# PMS_alpha_v0_1.net
KiCad netlist of a schematic drawn in EAGLE
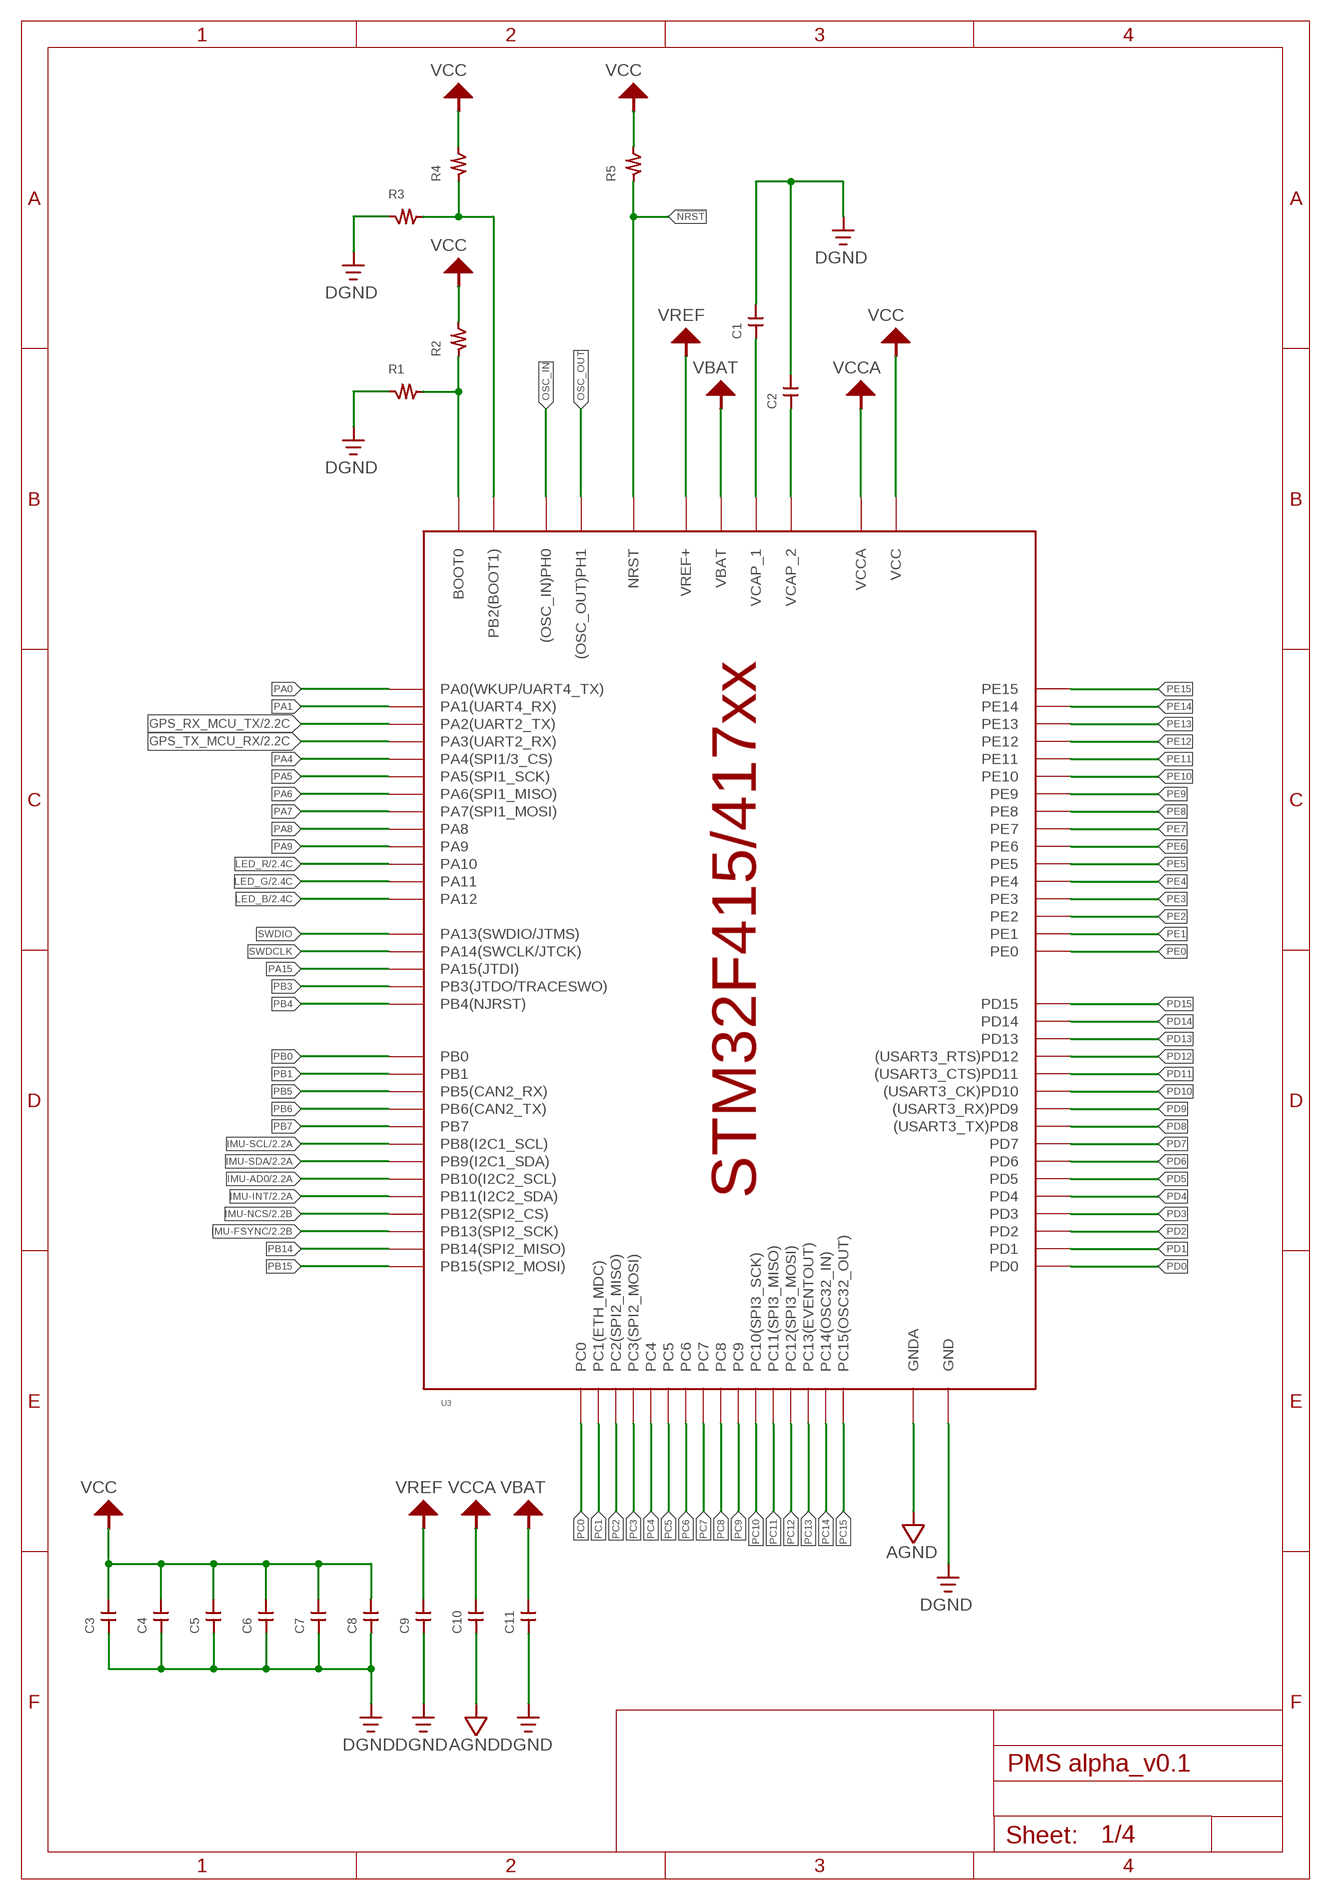
[diagram p0: schematic, sheet 1]
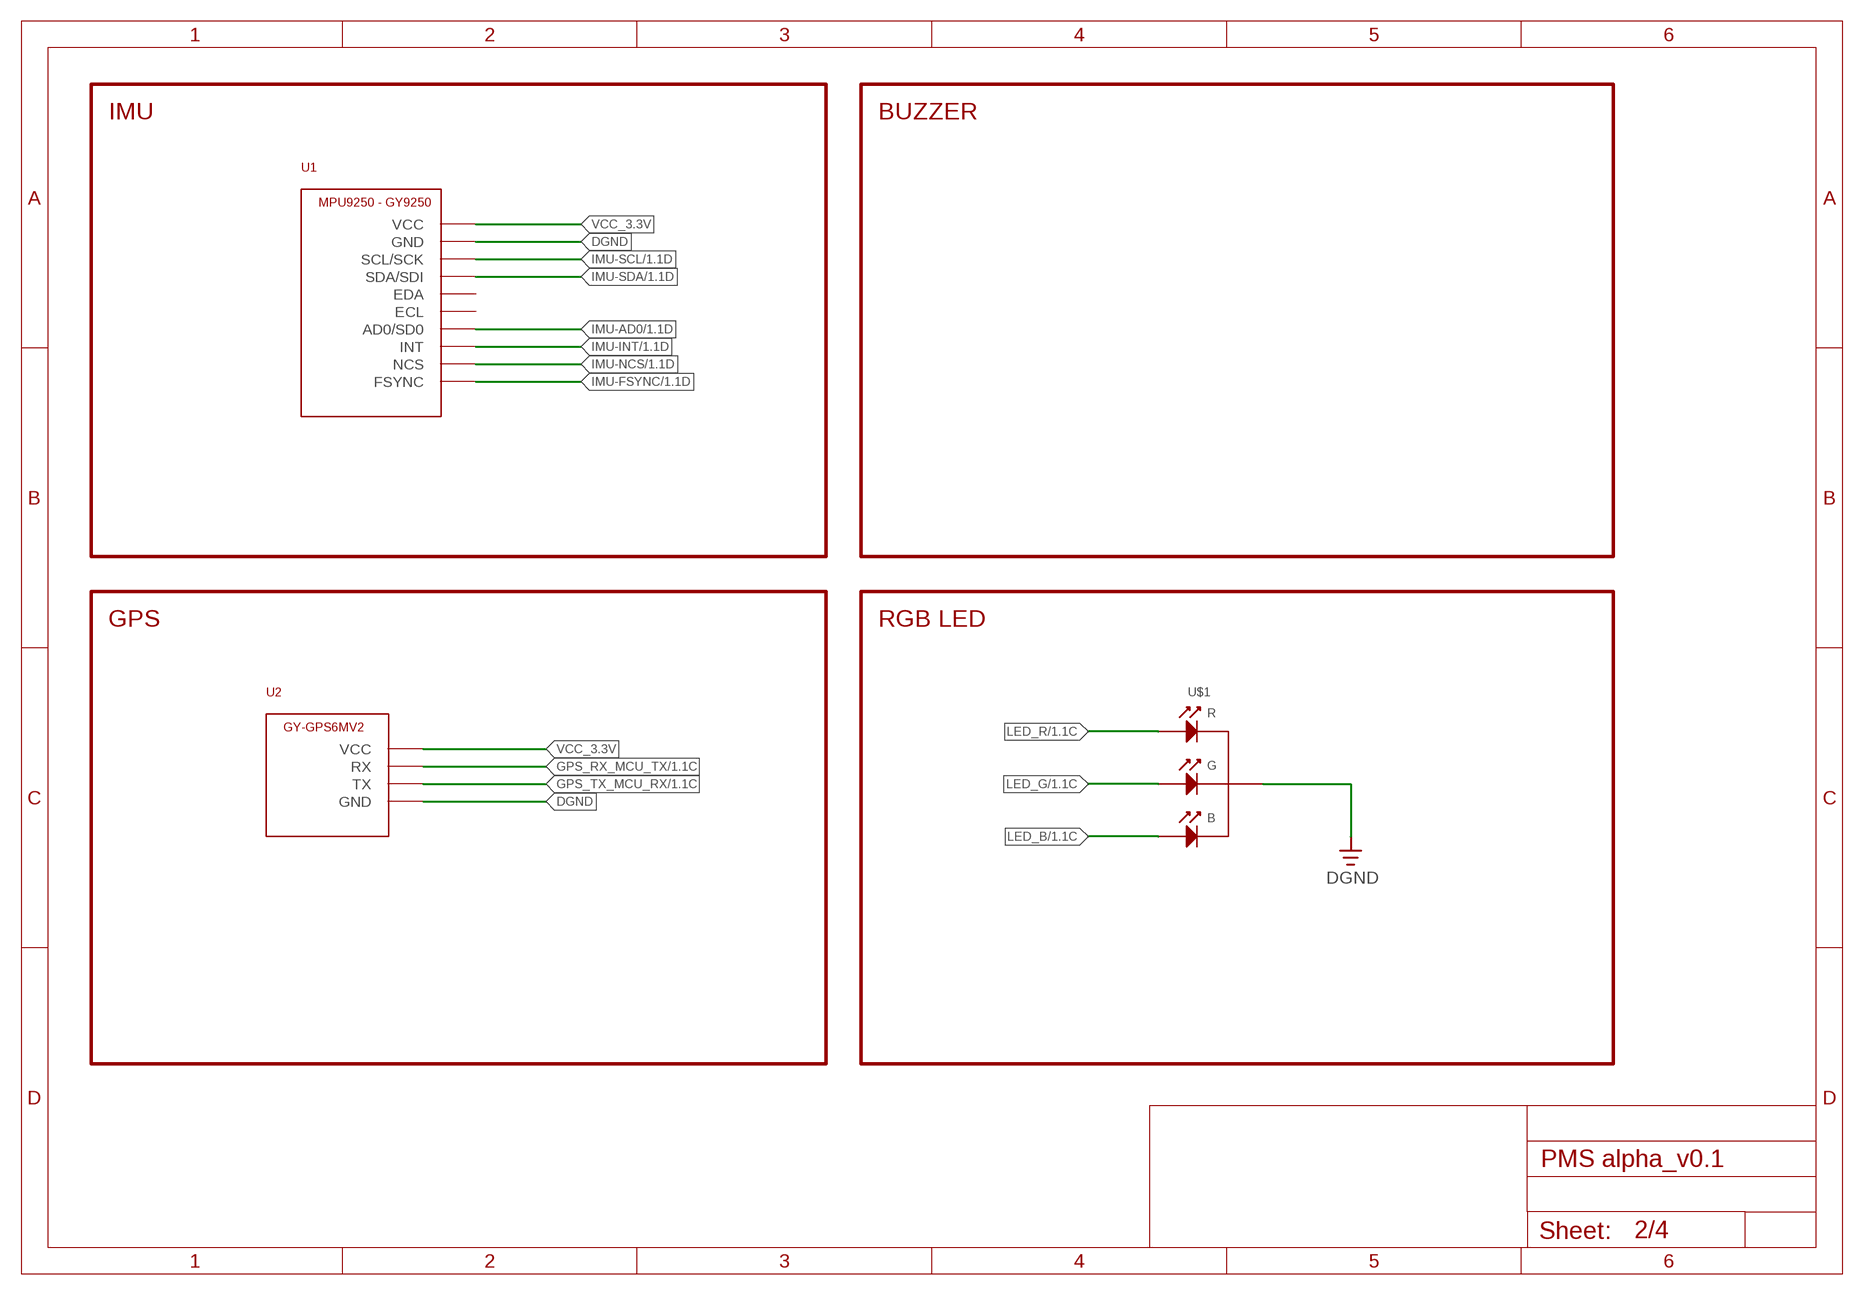
[diagram p1: schematic, sheet 2]
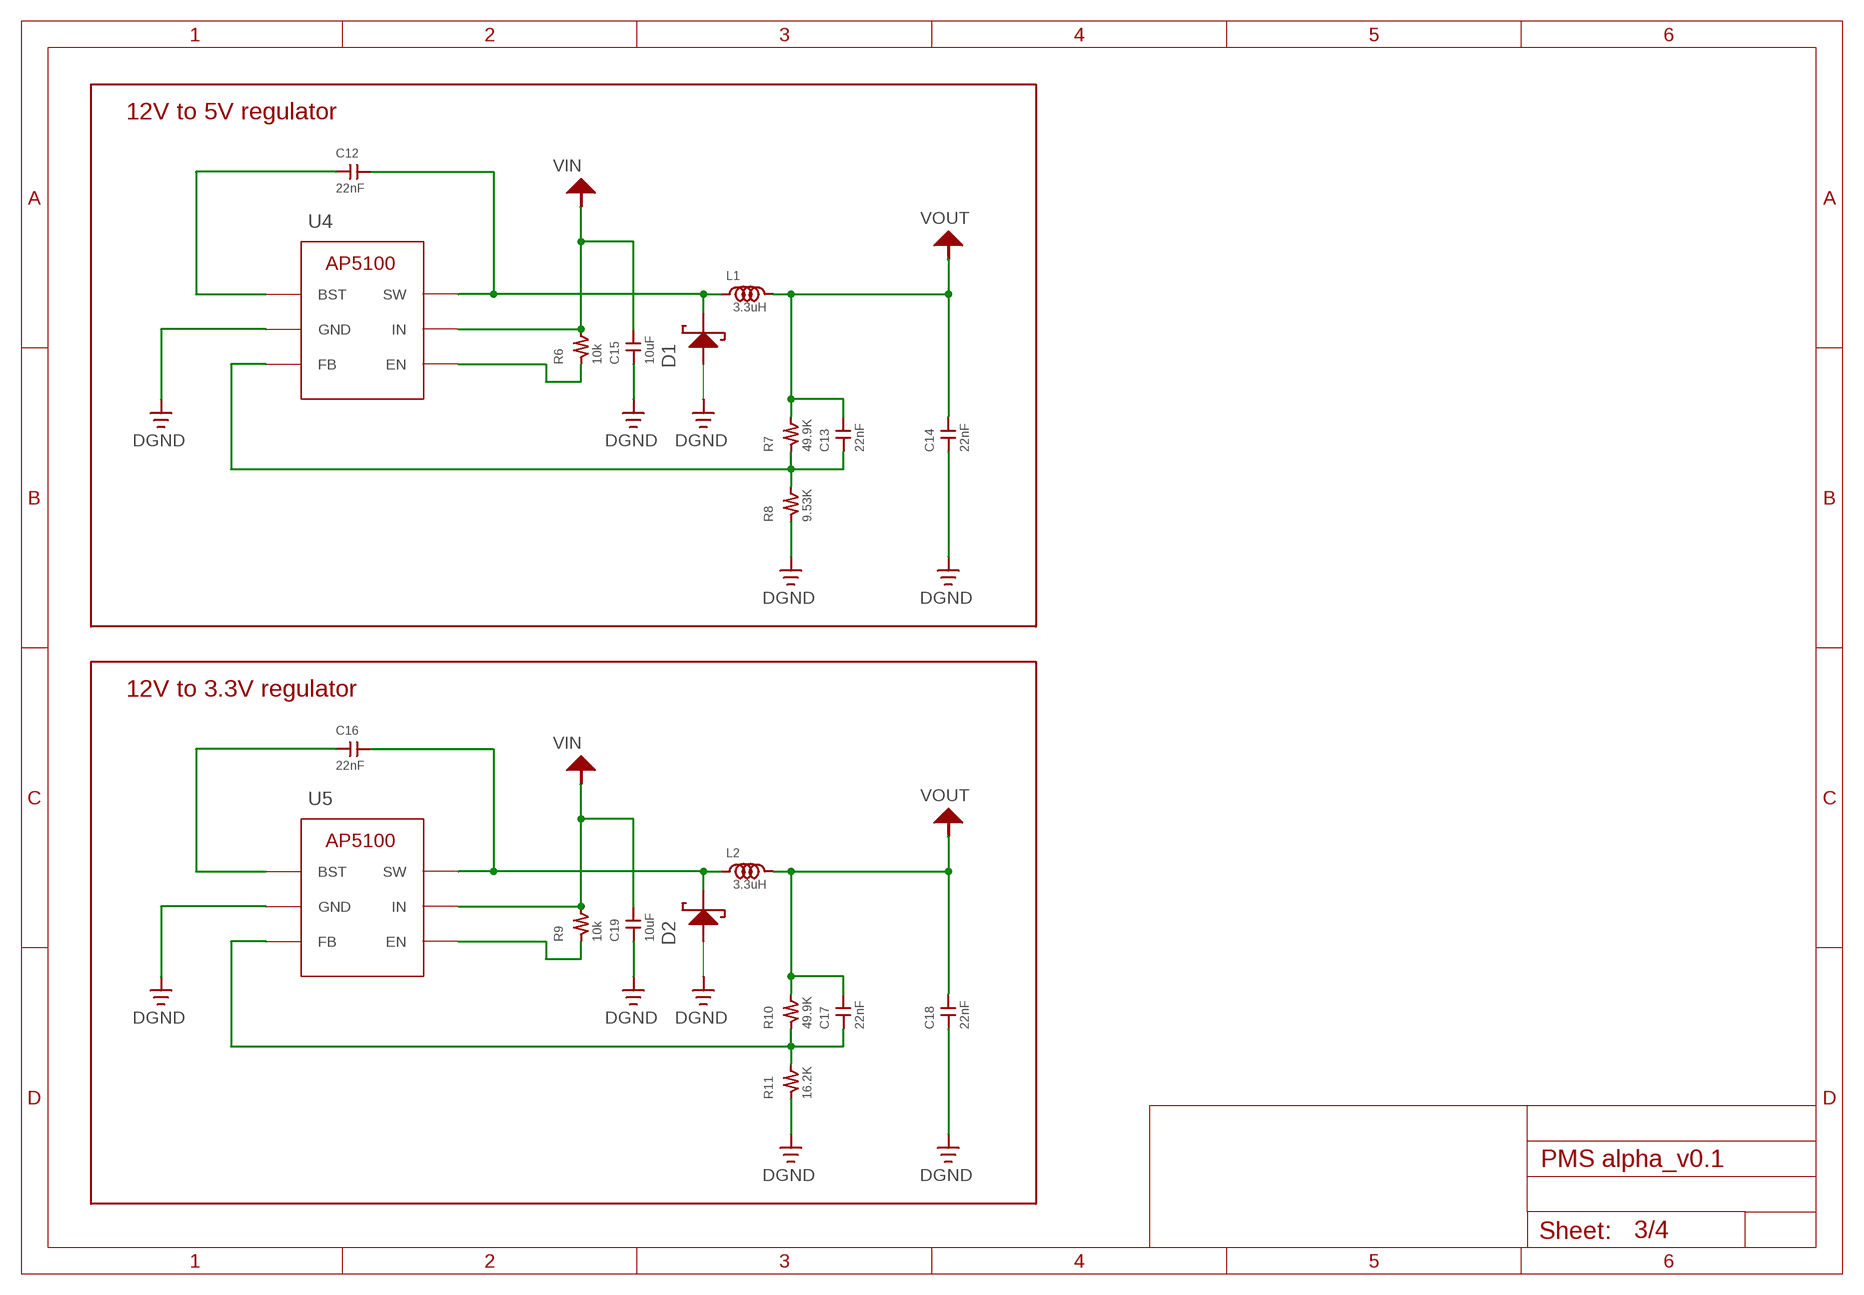
[diagram p2: schematic, sheet 3]
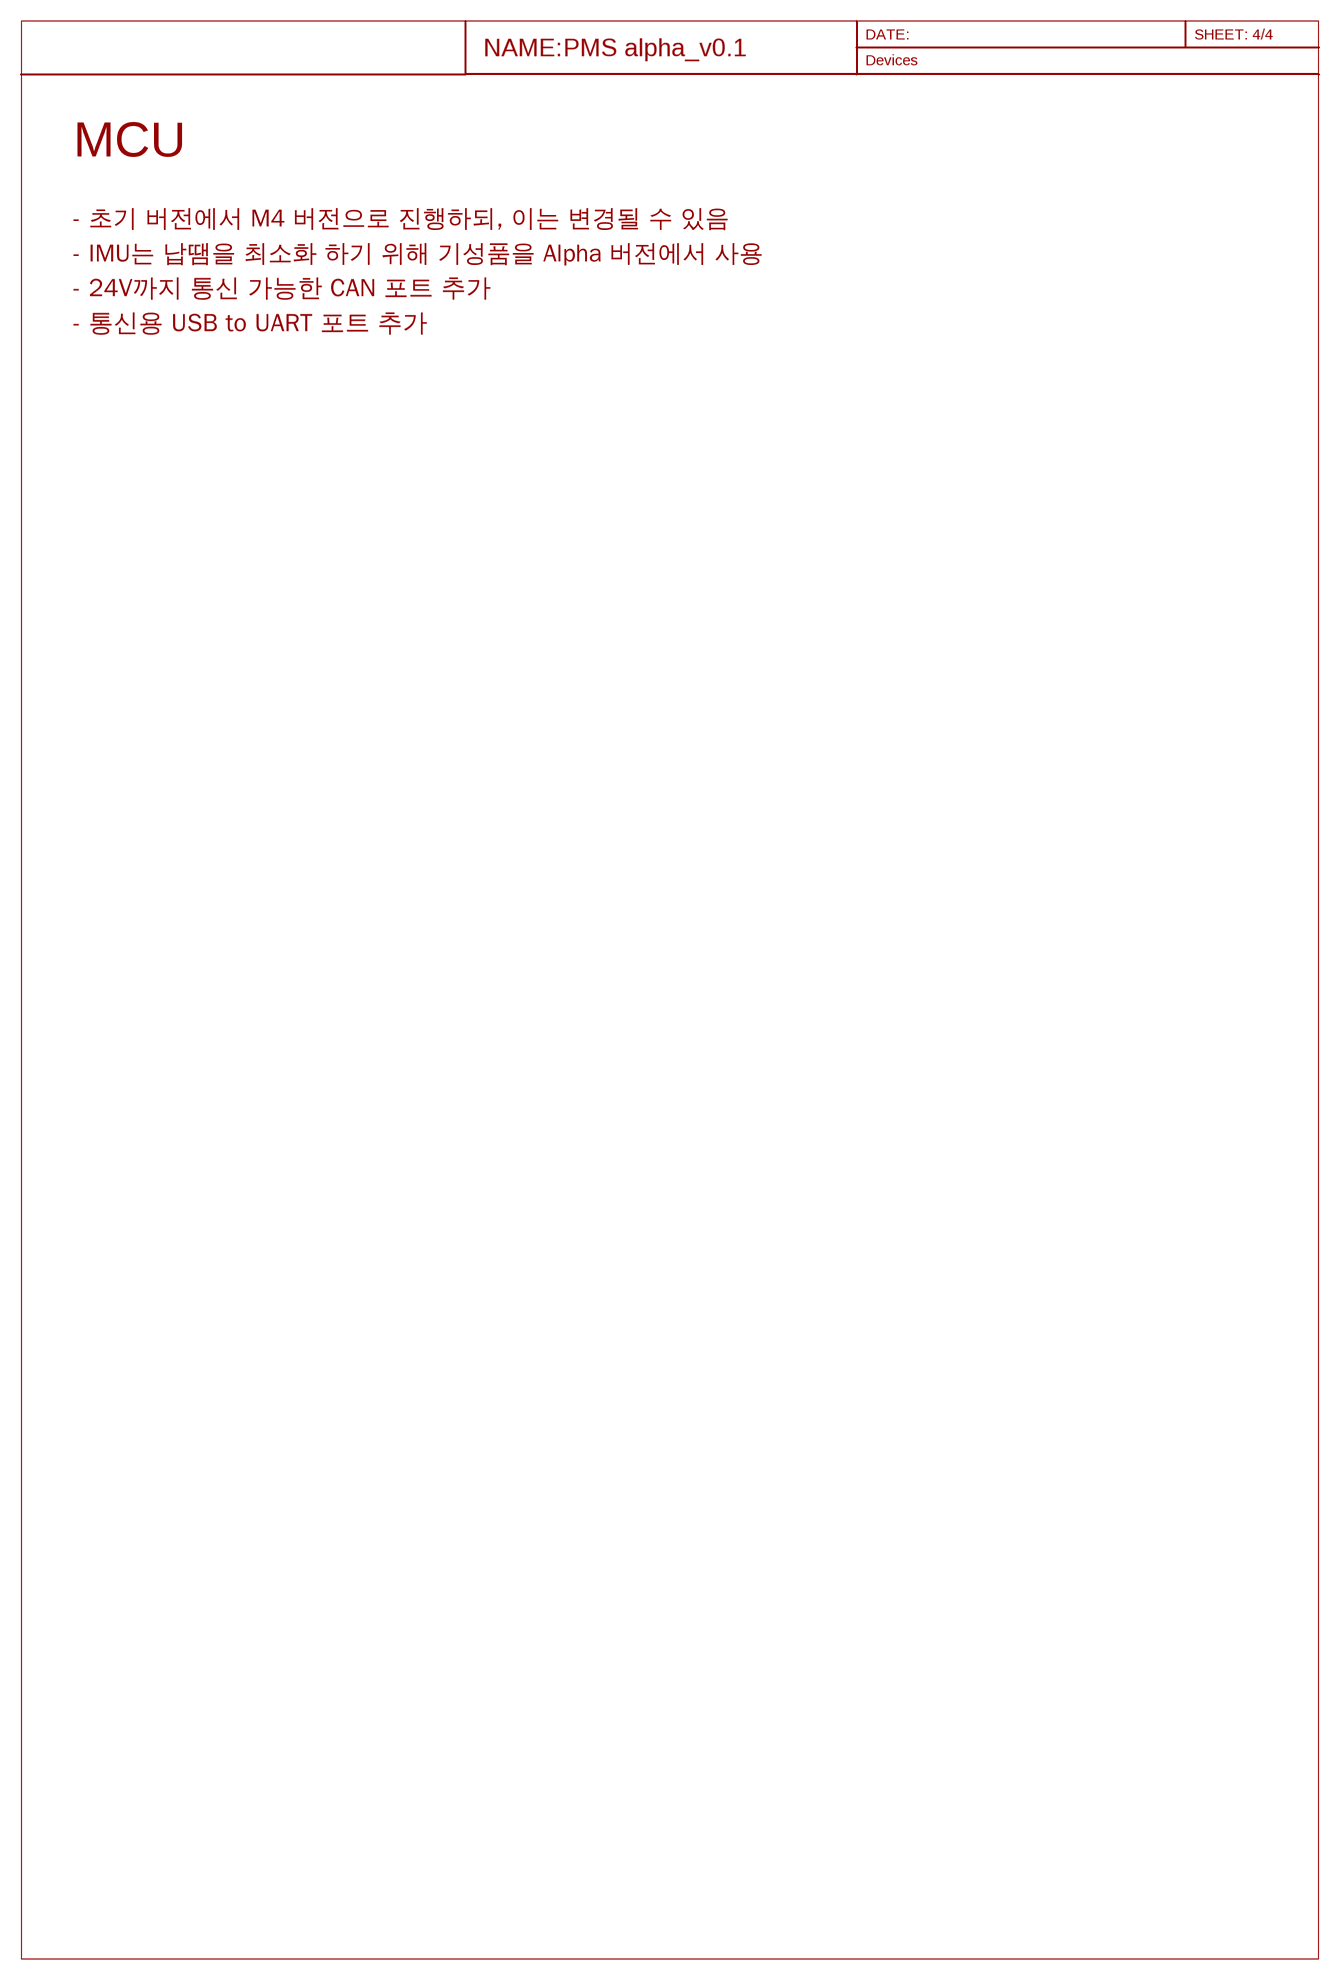
[diagram p3: schematic, sheet 4]

(export (version "E")
  (design (tool "Eeschema 10.0.6"))
  (components
    (comp (ref "U$1")
      (value "RGB_COM_K")
      (footprint "eagle-import:RGB_4PIN_2.5MM")
      (libsource (lib "eagle-import") (part "RGB_COM_K"))
    )
    (comp (ref "U1")
      (value "MPU-9250")
      (footprint "eagle-import:GY-9250")
      (libsource (lib "eagle-import") (part "MPU-9250"))
    )
    (comp (ref "U2")
      (value "GPS6MV2")
      (footprint "eagle-import:PAD_2.5MM")
      (libsource (lib "eagle-import") (part "GPS6MV2"))
    )
    (comp (ref "C1")
      (value "CAPACITOR_CHIP2012")
      (footprint "eagle-import:2012")
      (libsource (lib "eagle-import") (part "CAPACITOR_CHIP2012"))
    )
    (comp (ref "C2")
      (value "CAPACITOR_CHIP2012")
      (footprint "eagle-import:2012")
      (libsource (lib "eagle-import") (part "CAPACITOR_CHIP2012"))
    )
    (comp (ref "C3")
      (value "CAPACITOR_CHIP2012")
      (footprint "eagle-import:2012")
      (libsource (lib "eagle-import") (part "CAPACITOR_CHIP2012"))
    )
    (comp (ref "C4")
      (value "CAPACITOR_CHIP2012")
      (footprint "eagle-import:2012")
      (libsource (lib "eagle-import") (part "CAPACITOR_CHIP2012"))
    )
    (comp (ref "C5")
      (value "CAPACITOR_CHIP2012")
      (footprint "eagle-import:2012")
      (libsource (lib "eagle-import") (part "CAPACITOR_CHIP2012"))
    )
    (comp (ref "C6")
      (value "CAPACITOR_CHIP2012")
      (footprint "eagle-import:2012")
      (libsource (lib "eagle-import") (part "CAPACITOR_CHIP2012"))
    )
    (comp (ref "C7")
      (value "CAPACITOR_CHIP2012")
      (footprint "eagle-import:2012")
      (libsource (lib "eagle-import") (part "CAPACITOR_CHIP2012"))
    )
    (comp (ref "C8")
      (value "CAPACITOR_CHIP2012")
      (footprint "eagle-import:2012")
      (libsource (lib "eagle-import") (part "CAPACITOR_CHIP2012"))
    )
    (comp (ref "C9")
      (value "CAPACITOR_CHIP2012")
      (footprint "eagle-import:2012")
      (libsource (lib "eagle-import") (part "CAPACITOR_CHIP2012"))
    )
    (comp (ref "C10")
      (value "CAPACITOR_CHIP2012")
      (footprint "eagle-import:2012")
      (libsource (lib "eagle-import") (part "CAPACITOR_CHIP2012"))
    )
    (comp (ref "C11")
      (value "CAPACITOR_CHIP2012")
      (footprint "eagle-import:2012")
      (libsource (lib "eagle-import") (part "CAPACITOR_CHIP2012"))
    )
    (comp (ref "R1")
      (value "RESISTOR_CHIP_2012")
      (footprint "eagle-import:2012")
      (libsource (lib "eagle-import") (part "RESISTOR_CHIP_2012"))
    )
    (comp (ref "R2")
      (value "RESISTOR_CHIP_2012")
      (footprint "eagle-import:2012")
      (libsource (lib "eagle-import") (part "RESISTOR_CHIP_2012"))
    )
    (comp (ref "R3")
      (value "RESISTOR_CHIP_2012")
      (footprint "eagle-import:2012")
      (libsource (lib "eagle-import") (part "RESISTOR_CHIP_2012"))
    )
    (comp (ref "R4")
      (value "RESISTOR_CHIP_2012")
      (footprint "eagle-import:2012")
      (libsource (lib "eagle-import") (part "RESISTOR_CHIP_2012"))
    )
    (comp (ref "R5")
      (value "RESISTOR_CHIP_2012")
      (footprint "eagle-import:2012")
      (libsource (lib "eagle-import") (part "RESISTOR_CHIP_2012"))
    )
    (comp (ref "U3")
      (value "STM32F415/417")
      (footprint "eagle-import:LQFP100")
      (libsource (lib "eagle-import") (part "STM32F415/417"))
    )
    (comp (ref "C12")
      (value "22nF")
      (footprint "eagle-import:2012")
      (libsource (lib "eagle-import") (part "CAPACITOR_CHIP2012"))
    )
    (comp (ref "C13")
      (value "22nF")
      (footprint "eagle-import:2012")
      (libsource (lib "eagle-import") (part "CAPACITOR_CHIP2012"))
    )
    (comp (ref "C14")
      (value "22nF")
      (footprint "eagle-import:2012")
      (libsource (lib "eagle-import") (part "CAPACITOR_CHIP2012"))
    )
    (comp (ref "C15")
      (value "10uF")
      (footprint "eagle-import:2012")
      (libsource (lib "eagle-import") (part "CAPACITOR_CHIP2012"))
    )
    (comp (ref "C16")
      (value "22nF")
      (footprint "eagle-import:2012")
      (libsource (lib "eagle-import") (part "CAPACITOR_CHIP2012"))
    )
    (comp (ref "C17")
      (value "22nF")
      (footprint "eagle-import:2012")
      (libsource (lib "eagle-import") (part "CAPACITOR_CHIP2012"))
    )
    (comp (ref "C18")
      (value "22nF")
      (footprint "eagle-import:2012")
      (libsource (lib "eagle-import") (part "CAPACITOR_CHIP2012"))
    )
    (comp (ref "C19")
      (value "10uF")
      (footprint "eagle-import:2012")
      (libsource (lib "eagle-import") (part "CAPACITOR_CHIP2012"))
    )
    (comp (ref "D1")
      (value "BAT60JFILM")
      (footprint "eagle-import:SOD323")
      (libsource (lib "eagle-import") (part "BAT60JFILM"))
    )
    (comp (ref "D2")
      (value "BAT60JFILM")
      (footprint "eagle-import:SOD323")
      (libsource (lib "eagle-import") (part "BAT60JFILM"))
    )
    (comp (ref "L1")
      (value "3.3uH")
      (footprint "eagle-import:2012")
      (libsource (lib "eagle-import") (part "INDUCTOR2012"))
    )
    (comp (ref "L2")
      (value "3.3uH")
      (footprint "eagle-import:2012")
      (libsource (lib "eagle-import") (part "INDUCTOR2012"))
    )
    (comp (ref "R6")
      (value "10k")
      (footprint "eagle-import:2012")
      (libsource (lib "eagle-import") (part "RESISTOR_CHIP_2012"))
    )
    (comp (ref "R7")
      (value "49.9K")
      (footprint "eagle-import:2012")
      (libsource (lib "eagle-import") (part "RESISTOR_CHIP_2012"))
    )
    (comp (ref "R8")
      (value "9.53K")
      (footprint "eagle-import:2012")
      (libsource (lib "eagle-import") (part "RESISTOR_CHIP_2012"))
    )
    (comp (ref "R9")
      (value "10k")
      (footprint "eagle-import:2012")
      (libsource (lib "eagle-import") (part "RESISTOR_CHIP_2012"))
    )
    (comp (ref "R10")
      (value "49.9K")
      (footprint "eagle-import:2012")
      (libsource (lib "eagle-import") (part "RESISTOR_CHIP_2012"))
    )
    (comp (ref "R11")
      (value "16.2K")
      (footprint "eagle-import:2012")
      (libsource (lib "eagle-import") (part "RESISTOR_CHIP_2012"))
    )
    (comp (ref "U4")
      (value "AP5100")
      (footprint "eagle-import:SOT-26")
      (libsource (lib "eagle-import") (part "AP5100"))
    )
    (comp (ref "U5")
      (value "AP5100")
      (footprint "eagle-import:SOT-26")
      (libsource (lib "eagle-import") (part "AP5100"))
    )
  )
  (nets
    (net (code "1") (name "AGND") (class "Default")
      (node (ref "C10") (pin "P$1") (pinfunction "P$1_P$1") (pintype "passive"))
      (node (ref "U3") (pin "P$20") (pinfunction "GNDA_P$20") (pintype "power_in"))
    )
    (net (code "2") (name "DGND") (class "Default")
      (node (ref "C1") (pin "P$2") (pinfunction "P$2_P$2") (pintype "passive"))
      (node (ref "C11") (pin "P$1") (pinfunction "P$1_P$1") (pintype "passive"))
      (node (ref "C14") (pin "P$1") (pinfunction "P$1_P$1") (pintype "passive"))
      (node (ref "C15") (pin "P$1") (pinfunction "P$1_P$1") (pintype "passive"))
      (node (ref "C18") (pin "P$1") (pinfunction "P$1_P$1") (pintype "passive"))
      (node (ref "C19") (pin "P$1") (pinfunction "P$1_P$1") (pintype "passive"))
      (node (ref "C2") (pin "P$2") (pinfunction "P$2_P$2") (pintype "passive"))
      (node (ref "C3") (pin "P$1") (pinfunction "P$1_P$1") (pintype "passive"))
      (node (ref "C4") (pin "P$1") (pinfunction "P$1_P$1") (pintype "passive"))
      (node (ref "C5") (pin "P$1") (pinfunction "P$1_P$1") (pintype "passive"))
      (node (ref "C6") (pin "P$1") (pinfunction "P$1_P$1") (pintype "passive"))
      (node (ref "C7") (pin "P$1") (pinfunction "P$1_P$1") (pintype "passive"))
      (node (ref "C8") (pin "P$1") (pinfunction "P$1_P$1") (pintype "passive"))
      (node (ref "C9") (pin "P$1") (pinfunction "P$1_P$1") (pintype "passive"))
      (node (ref "D1") (pin "A") (pinfunction "A_A") (pintype "passive"))
      (node (ref "D2") (pin "A") (pinfunction "A_A") (pintype "passive"))
      (node (ref "R1") (pin "P$1") (pinfunction "P$1_P$1") (pintype "passive"))
      (node (ref "R11") (pin "P$1") (pinfunction "P$1_P$1") (pintype "passive"))
      (node (ref "R3") (pin "P$1") (pinfunction "P$1_P$1") (pintype "passive"))
      (node (ref "R8") (pin "P$1") (pinfunction "P$1_P$1") (pintype "passive"))
      (node (ref "U$1") (pin "P$4") (pinfunction "K_P$4") (pintype "bidirectional"))
      (node (ref "U1") (pin "P$2") (pinfunction "GND_P$2") (pintype "power_in"))
      (node (ref "U2") (pin "P$4") (pinfunction "GND_P$4") (pintype "power_in"))
      (node (ref "U3") (pin "P$10") (pinfunction "GND_P$10") (pintype "power_in"))
      (node (ref "U3") (pin "P$27") (pinfunction "GND_P$27") (pintype "power_in"))
      (node (ref "U3") (pin "P$74") (pinfunction "GND_P$74") (pintype "power_in"))
      (node (ref "U3") (pin "P$99") (pinfunction "GND_P$99") (pintype "power_in"))
      (node (ref "U4") (pin "P2") (pinfunction "GND_P2") (pintype "power_in"))
      (node (ref "U5") (pin "P2") (pinfunction "GND_P2") (pintype "power_in"))
    )
    (net (code "3") (name "GPS_RX_MCU_TX") (class "Default")
      (node (ref "U2") (pin "P$2") (pinfunction "RX_P$2") (pintype "bidirectional"))
      (node (ref "U3") (pin "P$25") (pinfunction "PA2(UART2_TX)_P$25") (pintype "bidirectional"))
    )
    (net (code "4") (name "GPS_TX_MCU_RX") (class "Default")
      (node (ref "U2") (pin "P$3") (pinfunction "TX_P$3") (pintype "bidirectional"))
      (node (ref "U3") (pin "P$26") (pinfunction "PA3(UART2_RX)_P$26") (pintype "bidirectional"))
    )
    (net (code "5") (name "IMU-AD0") (class "Default")
      (node (ref "U1") (pin "P$7") (pinfunction "AD0/SD0_P$7") (pintype "bidirectional"))
      (node (ref "U3") (pin "P$47") (pinfunction "PB10(I2C2_SCL)_P$47") (pintype "bidirectional"))
    )
    (net (code "6") (name "IMU-FSYNC") (class "Default")
      (node (ref "U1") (pin "P$10") (pinfunction "FSYNC_P$10") (pintype "bidirectional"))
      (node (ref "U3") (pin "P$52") (pinfunction "PB13(SPI2_SCK)_P$52") (pintype "bidirectional"))
    )
    (net (code "7") (name "IMU-INT") (class "Default")
      (node (ref "U1") (pin "P$8") (pinfunction "INT_P$8") (pintype "bidirectional"))
      (node (ref "U3") (pin "P$48") (pinfunction "PB11(I2C2_SDA)_P$48") (pintype "bidirectional"))
    )
    (net (code "8") (name "IMU-NCS") (class "Default")
      (node (ref "U1") (pin "P$9") (pinfunction "NCS_P$9") (pintype "bidirectional"))
      (node (ref "U3") (pin "P$51") (pinfunction "PB12(SPI2_CS)_P$51") (pintype "bidirectional"))
    )
    (net (code "9") (name "IMU-SCL") (class "Default")
      (node (ref "U1") (pin "P$3") (pinfunction "SCL/SCK_P$3") (pintype "bidirectional"))
      (node (ref "U3") (pin "P$95") (pinfunction "PB8(I2C1_SCL)_P$95") (pintype "bidirectional"))
    )
    (net (code "10") (name "IMU-SDA") (class "Default")
      (node (ref "U1") (pin "P$4") (pinfunction "SDA/SDI_P$4") (pintype "bidirectional"))
      (node (ref "U3") (pin "P$96") (pinfunction "PB9(I2C1_SDA)_P$96") (pintype "bidirectional"))
    )
    (net (code "11") (name "LED_B") (class "Default")
      (node (ref "U$1") (pin "P$3") (pinfunction "A_P$3") (pintype "bidirectional"))
      (node (ref "U3") (pin "P$71") (pinfunction "PA12_P$71") (pintype "bidirectional"))
    )
    (net (code "12") (name "LED_G") (class "Default")
      (node (ref "U$1") (pin "P$2") (pinfunction "A_P$2") (pintype "bidirectional"))
      (node (ref "U3") (pin "P$70") (pinfunction "PA11_P$70") (pintype "bidirectional"))
    )
    (net (code "13") (name "LED_R") (class "Default")
      (node (ref "U$1") (pin "P$1") (pinfunction "A_P$1") (pintype "bidirectional"))
      (node (ref "U3") (pin "P$69") (pinfunction "PA10_P$69") (pintype "bidirectional"))
    )
    (net (code "14") (name "Net-(U3-BOOT0)") (class "Default")
      (node (ref "R1") (pin "P$2") (pinfunction "P$2_P$2") (pintype "passive"))
      (node (ref "R2") (pin "P$1") (pinfunction "P$1_P$1") (pintype "passive"))
      (node (ref "U3") (pin "P$94") (pinfunction "BOOT0_P$94") (pintype "bidirectional"))
    )
    (net (code "15") (name "Net-(U3-PB2(BOOT1))") (class "Default")
      (node (ref "R3") (pin "P$2") (pinfunction "P$2_P$2") (pintype "passive"))
      (node (ref "R4") (pin "P$1") (pinfunction "P$1_P$1") (pintype "passive"))
      (node (ref "U3") (pin "P$37") (pinfunction "PB2(BOOT1)_P$37") (pintype "bidirectional"))
    )
    (net (code "16") (name "Net-(U3-VCAP_1)") (class "Default")
      (node (ref "C1") (pin "P$1") (pinfunction "P$1_P$1") (pintype "passive"))
      (node (ref "U3") (pin "P$49") (pinfunction "VCAP_1_P$49") (pintype "power_in"))
    )
    (net (code "17") (name "Net-(U3-VCAP_2)") (class "Default")
      (node (ref "C2") (pin "P$1") (pinfunction "P$1_P$1") (pintype "passive"))
      (node (ref "U3") (pin "P$73") (pinfunction "VCAP_2_P$73") (pintype "power_in"))
    )
    (net (code "18") (name "Net-(U4-BST)") (class "Default")
      (node (ref "C12") (pin "P$1") (pinfunction "P$1_P$1") (pintype "passive"))
      (node (ref "U4") (pin "P1") (pinfunction "BST_P1") (pintype "bidirectional"))
    )
    (net (code "19") (name "Net-(U4-EN)") (class "Default")
      (node (ref "R6") (pin "P$1") (pinfunction "P$1_P$1") (pintype "passive"))
      (node (ref "U4") (pin "P4") (pinfunction "EN_P4") (pintype "bidirectional"))
    )
    (net (code "20") (name "Net-(U4-FB)") (class "Default")
      (node (ref "C13") (pin "P$1") (pinfunction "P$1_P$1") (pintype "passive"))
      (node (ref "R7") (pin "P$1") (pinfunction "P$1_P$1") (pintype "passive"))
      (node (ref "R8") (pin "P$2") (pinfunction "P$2_P$2") (pintype "passive"))
      (node (ref "U4") (pin "P3") (pinfunction "FB_P3") (pintype "bidirectional"))
    )
    (net (code "21") (name "Net-(U4-SW)") (class "Default")
      (node (ref "C12") (pin "P$2") (pinfunction "P$2_P$2") (pintype "passive"))
      (node (ref "D1") (pin "K") (pinfunction "K_K") (pintype "passive"))
      (node (ref "L1") (pin "P$1") (pinfunction "P$1_P$1") (pintype "passive"))
      (node (ref "U4") (pin "P6") (pinfunction "SW_P6") (pintype "bidirectional"))
    )
    (net (code "22") (name "Net-(U5-BST)") (class "Default")
      (node (ref "C16") (pin "P$1") (pinfunction "P$1_P$1") (pintype "passive"))
      (node (ref "U5") (pin "P1") (pinfunction "BST_P1") (pintype "bidirectional"))
    )
    (net (code "23") (name "Net-(U5-EN)") (class "Default")
      (node (ref "R9") (pin "P$1") (pinfunction "P$1_P$1") (pintype "passive"))
      (node (ref "U5") (pin "P4") (pinfunction "EN_P4") (pintype "bidirectional"))
    )
    (net (code "24") (name "Net-(U5-FB)") (class "Default")
      (node (ref "C17") (pin "P$1") (pinfunction "P$1_P$1") (pintype "passive"))
      (node (ref "R10") (pin "P$1") (pinfunction "P$1_P$1") (pintype "passive"))
      (node (ref "R11") (pin "P$2") (pinfunction "P$2_P$2") (pintype "passive"))
      (node (ref "U5") (pin "P3") (pinfunction "FB_P3") (pintype "bidirectional"))
    )
    (net (code "25") (name "Net-(U5-SW)") (class "Default")
      (node (ref "C16") (pin "P$2") (pinfunction "P$2_P$2") (pintype "passive"))
      (node (ref "D2") (pin "K") (pinfunction "K_K") (pintype "passive"))
      (node (ref "L2") (pin "P$1") (pinfunction "P$1_P$1") (pintype "passive"))
      (node (ref "U5") (pin "P6") (pinfunction "SW_P6") (pintype "bidirectional"))
    )
    (net (code "26") (name "OSC_IN") (class "Default")
      (node (ref "U3") (pin "P$12") (pinfunction "(OSC_IN)PH0_P$12") (pintype "bidirectional"))
    )
    (net (code "27") (name "OSC_OUT") (class "Default")
      (node (ref "U3") (pin "P$13") (pinfunction "(OSC_OUT)PH1_P$13") (pintype "bidirectional"))
    )
    (net (code "28") (name "PA0") (class "Default")
      (node (ref "U3") (pin "P$23") (pinfunction "PA0(WKUP/UART4_TX)_P$23") (pintype "bidirectional"))
    )
    (net (code "29") (name "PA1") (class "Default")
      (node (ref "U3") (pin "P$24") (pinfunction "PA1(UART4_RX)_P$24") (pintype "bidirectional"))
    )
    (net (code "30") (name "PA4") (class "Default")
      (node (ref "U3") (pin "P$29") (pinfunction "PA4(SPI1/3_CS)_P$29") (pintype "bidirectional"))
    )
    (net (code "31") (name "PA5") (class "Default")
      (node (ref "U3") (pin "P$30") (pinfunction "PA5(SPI1_SCK)_P$30") (pintype "bidirectional"))
    )
    (net (code "32") (name "PA6") (class "Default")
      (node (ref "U3") (pin "P$31") (pinfunction "PA6(SPI1_MISO)_P$31") (pintype "bidirectional"))
    )
    (net (code "33") (name "PA7") (class "Default")
      (node (ref "U3") (pin "P$32") (pinfunction "PA7(SPI1_MOSI)_P$32") (pintype "bidirectional"))
    )
    (net (code "34") (name "PA8") (class "Default")
      (node (ref "U3") (pin "P$67") (pinfunction "PA8_P$67") (pintype "bidirectional"))
    )
    (net (code "35") (name "PA9") (class "Default")
      (node (ref "U3") (pin "P$68") (pinfunction "PA9_P$68") (pintype "bidirectional"))
    )
    (net (code "36") (name "PA15") (class "Default")
      (node (ref "U3") (pin "P$77") (pinfunction "PA15(JTDI)_P$77") (pintype "bidirectional"))
    )
    (net (code "37") (name "PB0") (class "Default")
      (node (ref "U3") (pin "P$35") (pinfunction "PB0_P$35") (pintype "bidirectional"))
    )
    (net (code "38") (name "PB1") (class "Default")
      (node (ref "U3") (pin "P$36") (pinfunction "PB1_P$36") (pintype "bidirectional"))
    )
    (net (code "39") (name "PB3") (class "Default")
      (node (ref "U3") (pin "P$89") (pinfunction "PB3(JTDO/TRACESWO)_P$89") (pintype "bidirectional"))
    )
    (net (code "40") (name "PB4") (class "Default")
      (node (ref "U3") (pin "P$90") (pinfunction "PB4(NJRST)_P$90") (pintype "bidirectional"))
    )
    (net (code "41") (name "PB5") (class "Default")
      (node (ref "U3") (pin "P$91") (pinfunction "PB5(CAN2_RX)_P$91") (pintype "bidirectional"))
    )
    (net (code "42") (name "PB6") (class "Default")
      (node (ref "U3") (pin "P$92") (pinfunction "PB6(CAN2_TX)_P$92") (pintype "bidirectional"))
    )
    (net (code "43") (name "PB7") (class "Default")
      (node (ref "U3") (pin "P$93") (pinfunction "PB7_P$93") (pintype "bidirectional"))
    )
    (net (code "44") (name "PB14") (class "Default")
      (node (ref "U3") (pin "P$53") (pinfunction "PB14(SPI2_MISO)_P$53") (pintype "bidirectional"))
    )
    (net (code "45") (name "PB15") (class "Default")
      (node (ref "U3") (pin "P$54") (pinfunction "PB15(SPI2_MOSI)_P$54") (pintype "bidirectional"))
    )
    (net (code "46") (name "PC0") (class "Default")
      (node (ref "U3") (pin "P$15") (pinfunction "PC0_P$15") (pintype "bidirectional"))
    )
    (net (code "47") (name "PC1") (class "Default")
      (node (ref "U3") (pin "P$16") (pinfunction "PC1(ETH_MDC)_P$16") (pintype "bidirectional"))
    )
    (net (code "48") (name "PC2") (class "Default")
      (node (ref "U3") (pin "P$17") (pinfunction "PC2(SPI2_MISO)_P$17") (pintype "bidirectional"))
    )
    (net (code "49") (name "PC3") (class "Default")
      (node (ref "U3") (pin "P$18") (pinfunction "PC3(SPI2_MOSI)_P$18") (pintype "bidirectional"))
    )
    (net (code "50") (name "PC4") (class "Default")
      (node (ref "U3") (pin "P$33") (pinfunction "PC4_P$33") (pintype "bidirectional"))
    )
    (net (code "51") (name "PC5") (class "Default")
      (node (ref "U3") (pin "P$34") (pinfunction "PC5_P$34") (pintype "bidirectional"))
    )
    (net (code "52") (name "PC6") (class "Default")
      (node (ref "U3") (pin "P$63") (pinfunction "PC6_P$63") (pintype "bidirectional"))
    )
    (net (code "53") (name "PC7") (class "Default")
      (node (ref "U3") (pin "P$64") (pinfunction "PC7_P$64") (pintype "bidirectional"))
    )
    (net (code "54") (name "PC8") (class "Default")
      (node (ref "U3") (pin "P$65") (pinfunction "PC8_P$65") (pintype "bidirectional"))
    )
    (net (code "55") (name "PC9") (class "Default")
      (node (ref "U3") (pin "P$66") (pinfunction "PC9_P$66") (pintype "bidirectional"))
    )
    (net (code "56") (name "PC10") (class "Default")
      (node (ref "U3") (pin "P$78") (pinfunction "PC10(SPI3_SCK)_P$78") (pintype "bidirectional"))
    )
    (net (code "57") (name "PC11") (class "Default")
      (node (ref "U3") (pin "P$79") (pinfunction "PC11(SPI3_MISO)_P$79") (pintype "bidirectional"))
    )
    (net (code "58") (name "PC12") (class "Default")
      (node (ref "U3") (pin "P$80") (pinfunction "PC12(SPI3_MOSI)_P$80") (pintype "bidirectional"))
    )
    (net (code "59") (name "PC13") (class "Default")
      (node (ref "U3") (pin "P$7") (pinfunction "PC13(EVENTOUT)_P$7") (pintype "bidirectional"))
    )
    (net (code "60") (name "PC14") (class "Default")
      (node (ref "U3") (pin "P$8") (pinfunction "PC14(OSC32_IN)_P$8") (pintype "bidirectional"))
    )
    (net (code "61") (name "PC15") (class "Default")
      (node (ref "U3") (pin "P$9") (pinfunction "PC15(OSC32_OUT)_P$9") (pintype "bidirectional"))
    )
    (net (code "62") (name "PD0") (class "Default")
      (node (ref "U3") (pin "P$81") (pinfunction "PD0_P$81") (pintype "bidirectional"))
    )
    (net (code "63") (name "PD1") (class "Default")
      (node (ref "U3") (pin "P$82") (pinfunction "PD1_P$82") (pintype "bidirectional"))
    )
    (net (code "64") (name "PD2") (class "Default")
      (node (ref "U3") (pin "P$83") (pinfunction "PD2_P$83") (pintype "bidirectional"))
    )
    (net (code "65") (name "PD3") (class "Default")
      (node (ref "U3") (pin "P$84") (pinfunction "PD3_P$84") (pintype "bidirectional"))
    )
    (net (code "66") (name "PD4") (class "Default")
      (node (ref "U3") (pin "P$85") (pinfunction "PD4_P$85") (pintype "bidirectional"))
    )
    (net (code "67") (name "PD5") (class "Default")
      (node (ref "U3") (pin "P$86") (pinfunction "PD5_P$86") (pintype "bidirectional"))
    )
    (net (code "68") (name "PD6") (class "Default")
      (node (ref "U3") (pin "P$87") (pinfunction "PD6_P$87") (pintype "bidirectional"))
    )
    (net (code "69") (name "PD7") (class "Default")
      (node (ref "U3") (pin "P$88") (pinfunction "PD7_P$88") (pintype "bidirectional"))
    )
    (net (code "70") (name "PD8") (class "Default")
      (node (ref "U3") (pin "P$55") (pinfunction "(USART3_TX)PD8_P$55") (pintype "bidirectional"))
    )
    (net (code "71") (name "PD9") (class "Default")
      (node (ref "U3") (pin "P$56") (pinfunction "(USART3_RX)PD9_P$56") (pintype "bidirectional"))
    )
    (net (code "72") (name "PD10") (class "Default")
      (node (ref "U3") (pin "P$57") (pinfunction "(USART3_CK)PD10_P$57") (pintype "bidirectional"))
    )
    (net (code "73") (name "PD11") (class "Default")
      (node (ref "U3") (pin "P$58") (pinfunction "(USART3_CTS)PD11_P$58") (pintype "bidirectional"))
    )
    (net (code "74") (name "PD12") (class "Default")
      (node (ref "U3") (pin "P$59") (pinfunction "(USART3_RTS)PD12_P$59") (pintype "bidirectional"))
    )
    (net (code "75") (name "PD13") (class "Default")
      (node (ref "U3") (pin "P$60") (pinfunction "PD13_P$60") (pintype "bidirectional"))
    )
    (net (code "76") (name "PD14") (class "Default")
      (node (ref "U3") (pin "P$61") (pinfunction "PD14_P$61") (pintype "bidirectional"))
    )
    (net (code "77") (name "PD15") (class "Default")
      (node (ref "U3") (pin "P$62") (pinfunction "PD15_P$62") (pintype "bidirectional"))
    )
    (net (code "78") (name "PE0") (class "Default")
      (node (ref "U3") (pin "P$97") (pinfunction "PE0_P$97") (pintype "bidirectional"))
    )
    (net (code "79") (name "PE1") (class "Default")
      (node (ref "U3") (pin "P$98") (pinfunction "PE1_P$98") (pintype "bidirectional"))
    )
    (net (code "80") (name "PE2") (class "Default")
      (node (ref "U3") (pin "P$1") (pinfunction "PE2_P$1") (pintype "bidirectional"))
    )
    (net (code "81") (name "PE3") (class "Default")
      (node (ref "U3") (pin "P$2") (pinfunction "PE3_P$2") (pintype "bidirectional"))
    )
    (net (code "82") (name "PE4") (class "Default")
      (node (ref "U3") (pin "P$3") (pinfunction "PE4_P$3") (pintype "bidirectional"))
    )
    (net (code "83") (name "PE5") (class "Default")
      (node (ref "U3") (pin "P$4") (pinfunction "PE5_P$4") (pintype "bidirectional"))
    )
    (net (code "84") (name "PE6") (class "Default")
      (node (ref "U3") (pin "P$5") (pinfunction "PE6_P$5") (pintype "bidirectional"))
    )
    (net (code "85") (name "PE7") (class "Default")
      (node (ref "U3") (pin "P$38") (pinfunction "PE7_P$38") (pintype "bidirectional"))
    )
    (net (code "86") (name "PE8") (class "Default")
      (node (ref "U3") (pin "P$39") (pinfunction "PE8_P$39") (pintype "bidirectional"))
    )
    (net (code "87") (name "PE9") (class "Default")
      (node (ref "U3") (pin "P$40") (pinfunction "PE9_P$40") (pintype "bidirectional"))
    )
    (net (code "88") (name "PE10") (class "Default")
      (node (ref "U3") (pin "P$41") (pinfunction "PE10_P$41") (pintype "bidirectional"))
    )
    (net (code "89") (name "PE11") (class "Default")
      (node (ref "U3") (pin "P$42") (pinfunction "PE11_P$42") (pintype "bidirectional"))
    )
    (net (code "90") (name "PE12") (class "Default")
      (node (ref "U3") (pin "P$43") (pinfunction "PE12_P$43") (pintype "bidirectional"))
    )
    (net (code "91") (name "PE13") (class "Default")
      (node (ref "U3") (pin "P$44") (pinfunction "PE13_P$44") (pintype "bidirectional"))
    )
    (net (code "92") (name "PE14") (class "Default")
      (node (ref "U3") (pin "P$45") (pinfunction "PE14_P$45") (pintype "bidirectional"))
    )
    (net (code "93") (name "PE15") (class "Default")
      (node (ref "U3") (pin "P$46") (pinfunction "PE15_P$46") (pintype "bidirectional"))
    )
    (net (code "94") (name "SWDCLK") (class "Default")
      (node (ref "U3") (pin "P$76") (pinfunction "PA14(SWCLK/JTCK)_P$76") (pintype "bidirectional"))
    )
    (net (code "95") (name "SWDIO") (class "Default")
      (node (ref "U3") (pin "P$72") (pinfunction "PA13(SWDIO/JTMS)_P$72") (pintype "bidirectional"))
    )
    (net (code "96") (name "VBAT") (class "Default")
      (node (ref "C11") (pin "P$2") (pinfunction "P$2_P$2") (pintype "passive"))
      (node (ref "U3") (pin "P$6") (pinfunction "VBAT_P$6") (pintype "power_in"))
    )
    (net (code "97") (name "VCCA") (class "Default")
      (node (ref "C10") (pin "P$2") (pinfunction "P$2_P$2") (pintype "passive"))
      (node (ref "U3") (pin "P$22") (pinfunction "VCCA_P$22") (pintype "power_in"))
    )
    (net (code "98") (name "VCC_3.3V") (class "Default")
      (node (ref "C3") (pin "P$2") (pinfunction "P$2_P$2") (pintype "passive"))
      (node (ref "C4") (pin "P$2") (pinfunction "P$2_P$2") (pintype "passive"))
      (node (ref "C5") (pin "P$2") (pinfunction "P$2_P$2") (pintype "passive"))
      (node (ref "C6") (pin "P$2") (pinfunction "P$2_P$2") (pintype "passive"))
      (node (ref "C7") (pin "P$2") (pinfunction "P$2_P$2") (pintype "passive"))
      (node (ref "C8") (pin "P$2") (pinfunction "P$2_P$2") (pintype "passive"))
      (node (ref "R2") (pin "P$2") (pinfunction "P$2_P$2") (pintype "passive"))
      (node (ref "R4") (pin "P$2") (pinfunction "P$2_P$2") (pintype "passive"))
      (node (ref "R5") (pin "P$2") (pinfunction "P$2_P$2") (pintype "passive"))
      (node (ref "U1") (pin "P$1") (pinfunction "VCC_P$1") (pintype "power_in"))
      (node (ref "U2") (pin "P$1") (pinfunction "VCC_P$1") (pintype "power_in"))
      (node (ref "U3") (pin "P$100") (pinfunction "VCC_P$100") (pintype "power_in"))
      (node (ref "U3") (pin "P$11") (pinfunction "VCC_P$11") (pintype "power_in"))
      (node (ref "U3") (pin "P$19") (pinfunction "VCC_P$19") (pintype "power_in"))
      (node (ref "U3") (pin "P$28") (pinfunction "VCC_P$28") (pintype "power_in"))
      (node (ref "U3") (pin "P$50") (pinfunction "VCC_P$50") (pintype "power_in"))
      (node (ref "U3") (pin "P$75") (pinfunction "VCC_P$75") (pintype "power_in"))
    )
    (net (code "99") (name "VIN") (class "Default")
      (node (ref "C15") (pin "P$2") (pinfunction "P$2_P$2") (pintype "passive"))
      (node (ref "C19") (pin "P$2") (pinfunction "P$2_P$2") (pintype "passive"))
      (node (ref "R6") (pin "P$2") (pinfunction "P$2_P$2") (pintype "passive"))
      (node (ref "R9") (pin "P$2") (pinfunction "P$2_P$2") (pintype "passive"))
      (node (ref "U4") (pin "P5") (pinfunction "IN_P5") (pintype "bidirectional"))
      (node (ref "U5") (pin "P5") (pinfunction "IN_P5") (pintype "bidirectional"))
    )
    (net (code "100") (name "VOUT") (class "Default")
      (node (ref "C13") (pin "P$2") (pinfunction "P$2_P$2") (pintype "passive"))
      (node (ref "C14") (pin "P$2") (pinfunction "P$2_P$2") (pintype "passive"))
      (node (ref "C17") (pin "P$2") (pinfunction "P$2_P$2") (pintype "passive"))
      (node (ref "C18") (pin "P$2") (pinfunction "P$2_P$2") (pintype "passive"))
      (node (ref "L1") (pin "P$2") (pinfunction "P$2_P$2") (pintype "passive"))
      (node (ref "L2") (pin "P$2") (pinfunction "P$2_P$2") (pintype "passive"))
      (node (ref "R10") (pin "P$2") (pinfunction "P$2_P$2") (pintype "passive"))
      (node (ref "R7") (pin "P$2") (pinfunction "P$2_P$2") (pintype "passive"))
    )
    (net (code "101") (name "VREF") (class "Default")
      (node (ref "C9") (pin "P$2") (pinfunction "P$2_P$2") (pintype "passive"))
      (node (ref "U3") (pin "P$21") (pinfunction "VREF+_P$21") (pintype "power_in"))
    )
    (net (code "102") (name "unconnected-(U1-ECL-PadP$6)") (class "Default")
      (node (ref "U1") (pin "P$6") (pinfunction "ECL_P$6") (pintype "bidirectional"))
    )
    (net (code "103") (name "unconnected-(U1-EDA-PadP$5)") (class "Default")
      (node (ref "U1") (pin "P$5") (pinfunction "EDA_P$5") (pintype "bidirectional"))
    )
    (net (code "104") (name "~{NRST}") (class "Default")
      (node (ref "R5") (pin "P$1") (pinfunction "P$1_P$1") (pintype "passive"))
      (node (ref "U3") (pin "P$14") (pinfunction "NRST_P$14") (pintype "bidirectional"))
    )
  )
)
